# SCH_cansat2025_2025-10-21.net
KiCad netlist of a schematic drawn in EasyEDA
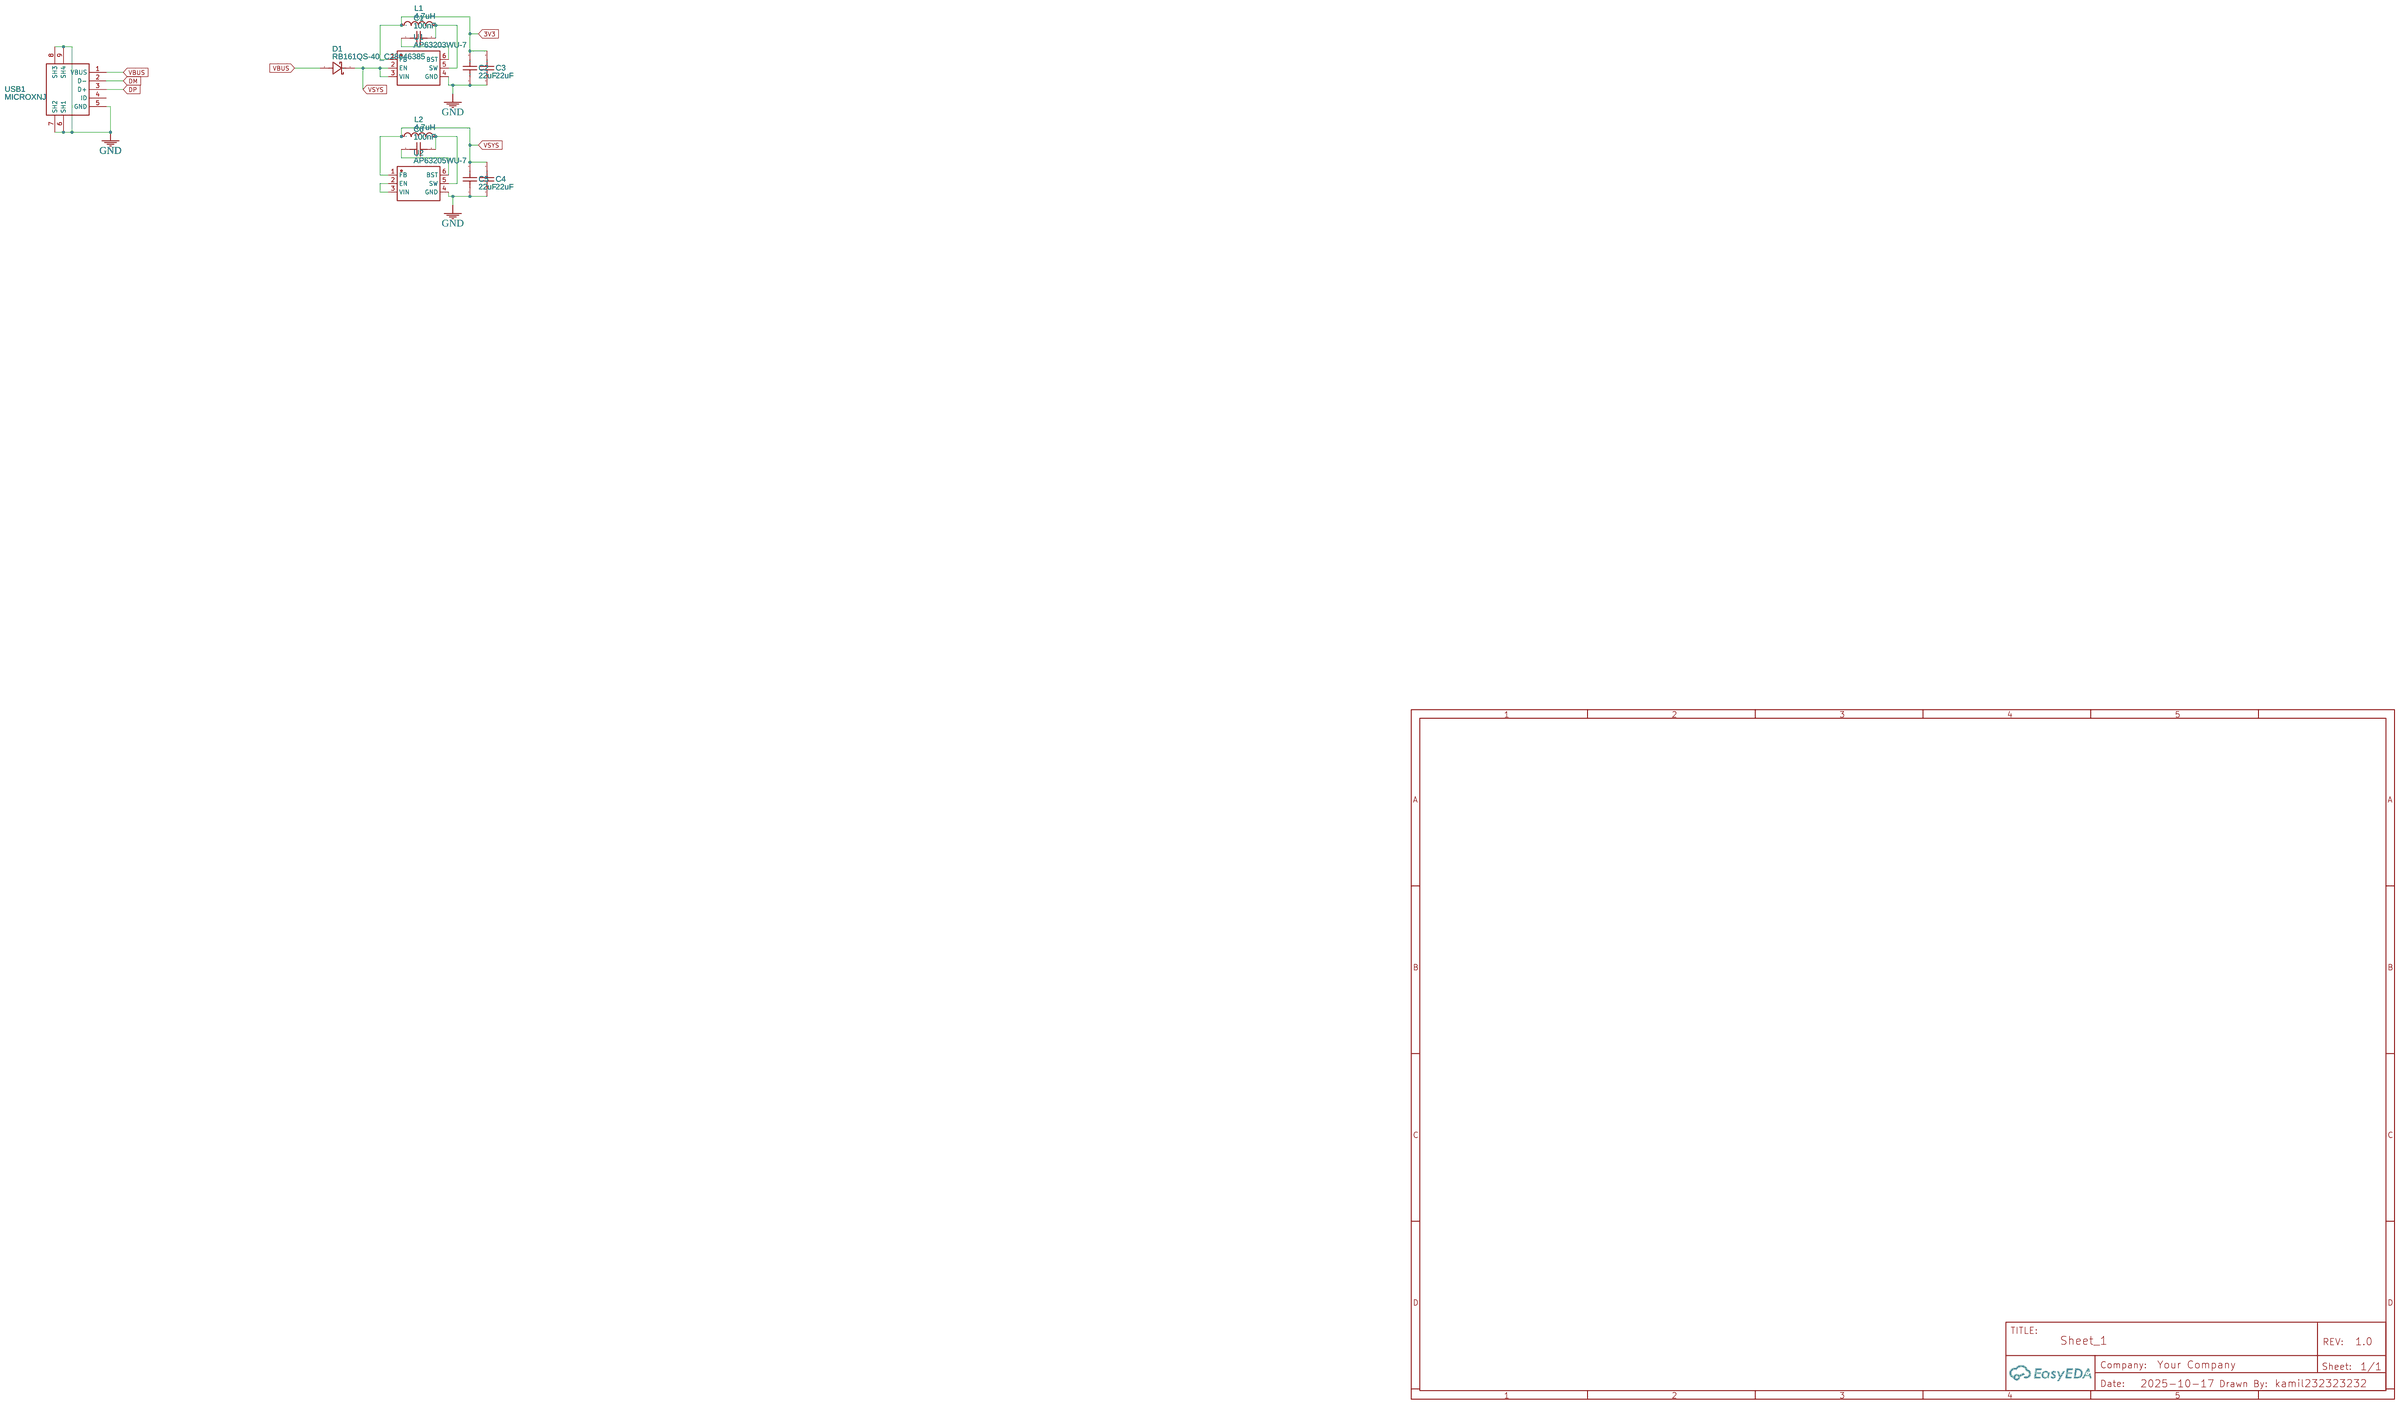
[diagram p0: schematic sheet]

(export (version "E")
  (design (tool "Eeschema 10.0.6"))
  (components
    (comp (ref "C1")
      (value "100nF")
      (fields
        (field (name "Manufacturer Part") "FCC0402B104K160AT")
        (field (name "Manufacturer") "FOJAN(富捷)")
      )
      (libsource (lib "") (part "FCC0402B104K160AT"))
    )
    (comp (ref "C2")
      (value "22uF")
      (fields
        (field (name "Manufacturer Part") "GRM155R60J226ME11D")
        (field (name "Manufacturer") "muRata(村田)")
      )
      (libsource (lib "") (part "GRM155R60J226ME11D"))
    )
    (comp (ref "C3")
      (value "22uF")
      (fields
        (field (name "Manufacturer Part") "GRM155R60J226ME11D")
        (field (name "Manufacturer") "muRata(村田)")
      )
      (libsource (lib "") (part "GRM155R60J226ME11D"))
    )
    (comp (ref "C4")
      (value "22uF")
      (fields
        (field (name "Manufacturer Part") "GRM155R60J226ME11D")
        (field (name "Manufacturer") "muRata(村田)")
      )
      (libsource (lib "") (part "GRM155R60J226ME11D"))
    )
    (comp (ref "C5")
      (value "22uF")
      (fields
        (field (name "Manufacturer Part") "GRM155R60J226ME11D")
        (field (name "Manufacturer") "muRata(村田)")
      )
      (libsource (lib "") (part "GRM155R60J226ME11D"))
    )
    (comp (ref "C6")
      (value "100nF")
      (fields
        (field (name "Manufacturer Part") "FCC0402B104K160AT")
        (field (name "Manufacturer") "FOJAN(富捷)")
      )
      (libsource (lib "") (part "FCC0402B104K160AT"))
    )
    (comp (ref "D1")
      (value "RB161QS-40_C28646385")
      (fields (field (name "Manufacturer Part") "RB161QS-40") (field (name "Manufacturer") "TECH PUBLIC(台舟)"))
      (libsource (lib "") (part "RB161QS-40_C28646385"))
    )
    (comp (ref "L1")
      (value "4.7uH")
      (fields (field (name "Manufacturer Part") "CMI201209U4R7KT") (field (name "Manufacturer") "FH(风华)"))
      (libsource (lib "") (part "CMI201209U4R7KT"))
    )
    (comp (ref "L2")
      (value "4.7uH")
      (fields (field (name "Manufacturer Part") "CMI201209U4R7KT") (field (name "Manufacturer") "FH(风华)"))
      (libsource (lib "") (part "CMI201209U4R7KT_1"))
    )
    (comp (ref "U1")
      (value "AP63203WU-7")
      (fields (field (name "Manufacturer") "DIODES(美台)"))
      (libsource (lib "") (part "AP63203WU-7"))
    )
    (comp (ref "U2")
      (value "AP63205WU-7")
      (fields (field (name "Manufacturer") "DIODES(美台)"))
      (libsource (lib "") (part "AP63205WU-7"))
    )
    (comp (ref "USB1")
      (value "MICROXNJ")
      (fields (field (name "Manufacturer Part") "MicroXNJ") (field (name "Manufacturer") "SHOU HAN(首韩)"))
      (libsource (lib "") (part "MICROXNJ"))
    )
  )
  (nets
    (net (code "1") (name "3V3") (class "Default")
      (node (ref "C2") (pin "2") (pinfunction "2_2") (pintype "unspecified"))
      (node (ref "C3") (pin "2") (pinfunction "2_2") (pintype "unspecified"))
      (node (ref "L1") (pin "1") (pinfunction "1_1") (pintype "unspecified"))
      (node (ref "U1") (pin "1") (pinfunction "FB_1") (pintype "unspecified"))
    )
    (net (code "2") (name "DM") (class "Default")
      (node (ref "USB1") (pin "2") (pinfunction "D-_2") (pintype "unspecified"))
    )
    (net (code "3") (name "DP") (class "Default")
      (node (ref "USB1") (pin "3") (pinfunction "D+_3") (pintype "unspecified"))
    )
    (net (code "4") (name "GND") (class "Default")
      (node (ref "C2") (pin "1") (pinfunction "1_1") (pintype "unspecified"))
      (node (ref "C3") (pin "1") (pinfunction "1_1") (pintype "unspecified"))
      (node (ref "C4") (pin "1") (pinfunction "1_1") (pintype "unspecified"))
      (node (ref "C5") (pin "1") (pinfunction "1_1") (pintype "unspecified"))
      (node (ref "U1") (pin "4") (pinfunction "GND_4") (pintype "unspecified"))
      (node (ref "U2") (pin "4") (pinfunction "GND_4") (pintype "unspecified"))
      (node (ref "USB1") (pin "5") (pinfunction "GND_5") (pintype "unspecified"))
      (node (ref "USB1") (pin "6") (pinfunction "SH1_6") (pintype "unspecified"))
      (node (ref "USB1") (pin "7") (pinfunction "SH2_7") (pintype "unspecified"))
      (node (ref "USB1") (pin "8") (pinfunction "SH3_8") (pintype "unspecified"))
      (node (ref "USB1") (pin "9") (pinfunction "SH4_9") (pintype "unspecified"))
    )
    (net (code "5") (name "Net-(U1-BST)") (class "Default")
      (node (ref "C1") (pin "1") (pinfunction "1_1") (pintype "unspecified"))
      (node (ref "U1") (pin "6") (pinfunction "BST_6") (pintype "unspecified"))
    )
    (net (code "6") (name "Net-(U1-SW)") (class "Default")
      (node (ref "C1") (pin "2") (pinfunction "2_2") (pintype "unspecified"))
      (node (ref "L1") (pin "2") (pinfunction "2_2") (pintype "unspecified"))
      (node (ref "U1") (pin "5") (pinfunction "SW_5") (pintype "unspecified"))
    )
    (net (code "7") (name "Net-(U2-BST)") (class "Default")
      (node (ref "C6") (pin "1") (pinfunction "1_1") (pintype "unspecified"))
      (node (ref "U2") (pin "6") (pinfunction "BST_6") (pintype "unspecified"))
    )
    (net (code "8") (name "Net-(U2-EN)") (class "Default")
      (node (ref "U2") (pin "2") (pinfunction "EN_2") (pintype "unspecified"))
      (node (ref "U2") (pin "3") (pinfunction "VIN_3") (pintype "unspecified"))
    )
    (net (code "9") (name "Net-(U2-SW)") (class "Default")
      (node (ref "C6") (pin "2") (pinfunction "2_2") (pintype "unspecified"))
      (node (ref "L2") (pin "2") (pinfunction "2_2") (pintype "unspecified"))
      (node (ref "U2") (pin "5") (pinfunction "SW_5") (pintype "unspecified"))
    )
    (net (code "10") (name "VBUS") (class "Default")
      (node (ref "D1") (pin "2") (pinfunction "A_2") (pintype "unspecified"))
      (node (ref "USB1") (pin "1") (pinfunction "VBUS_1") (pintype "unspecified"))
    )
    (net (code "11") (name "VSYS") (class "Default")
      (node (ref "C4") (pin "2") (pinfunction "2_2") (pintype "unspecified"))
      (node (ref "C5") (pin "2") (pinfunction "2_2") (pintype "unspecified"))
      (node (ref "D1") (pin "1") (pinfunction "C_1") (pintype "unspecified"))
      (node (ref "L2") (pin "1") (pinfunction "1_1") (pintype "unspecified"))
      (node (ref "U1") (pin "2") (pinfunction "EN_2") (pintype "unspecified"))
      (node (ref "U1") (pin "3") (pinfunction "VIN_3") (pintype "unspecified"))
      (node (ref "U2") (pin "1") (pinfunction "FB_1") (pintype "unspecified"))
    )
    (net (code "12") (name "unconnected-(USB1-ID-Pad4)") (class "Default")
      (node (ref "USB1") (pin "4") (pinfunction "ID_4") (pintype "unspecified"))
    )
  )
)
